# control_v26.net
KiCad netlist of a schematic drawn in EAGLE
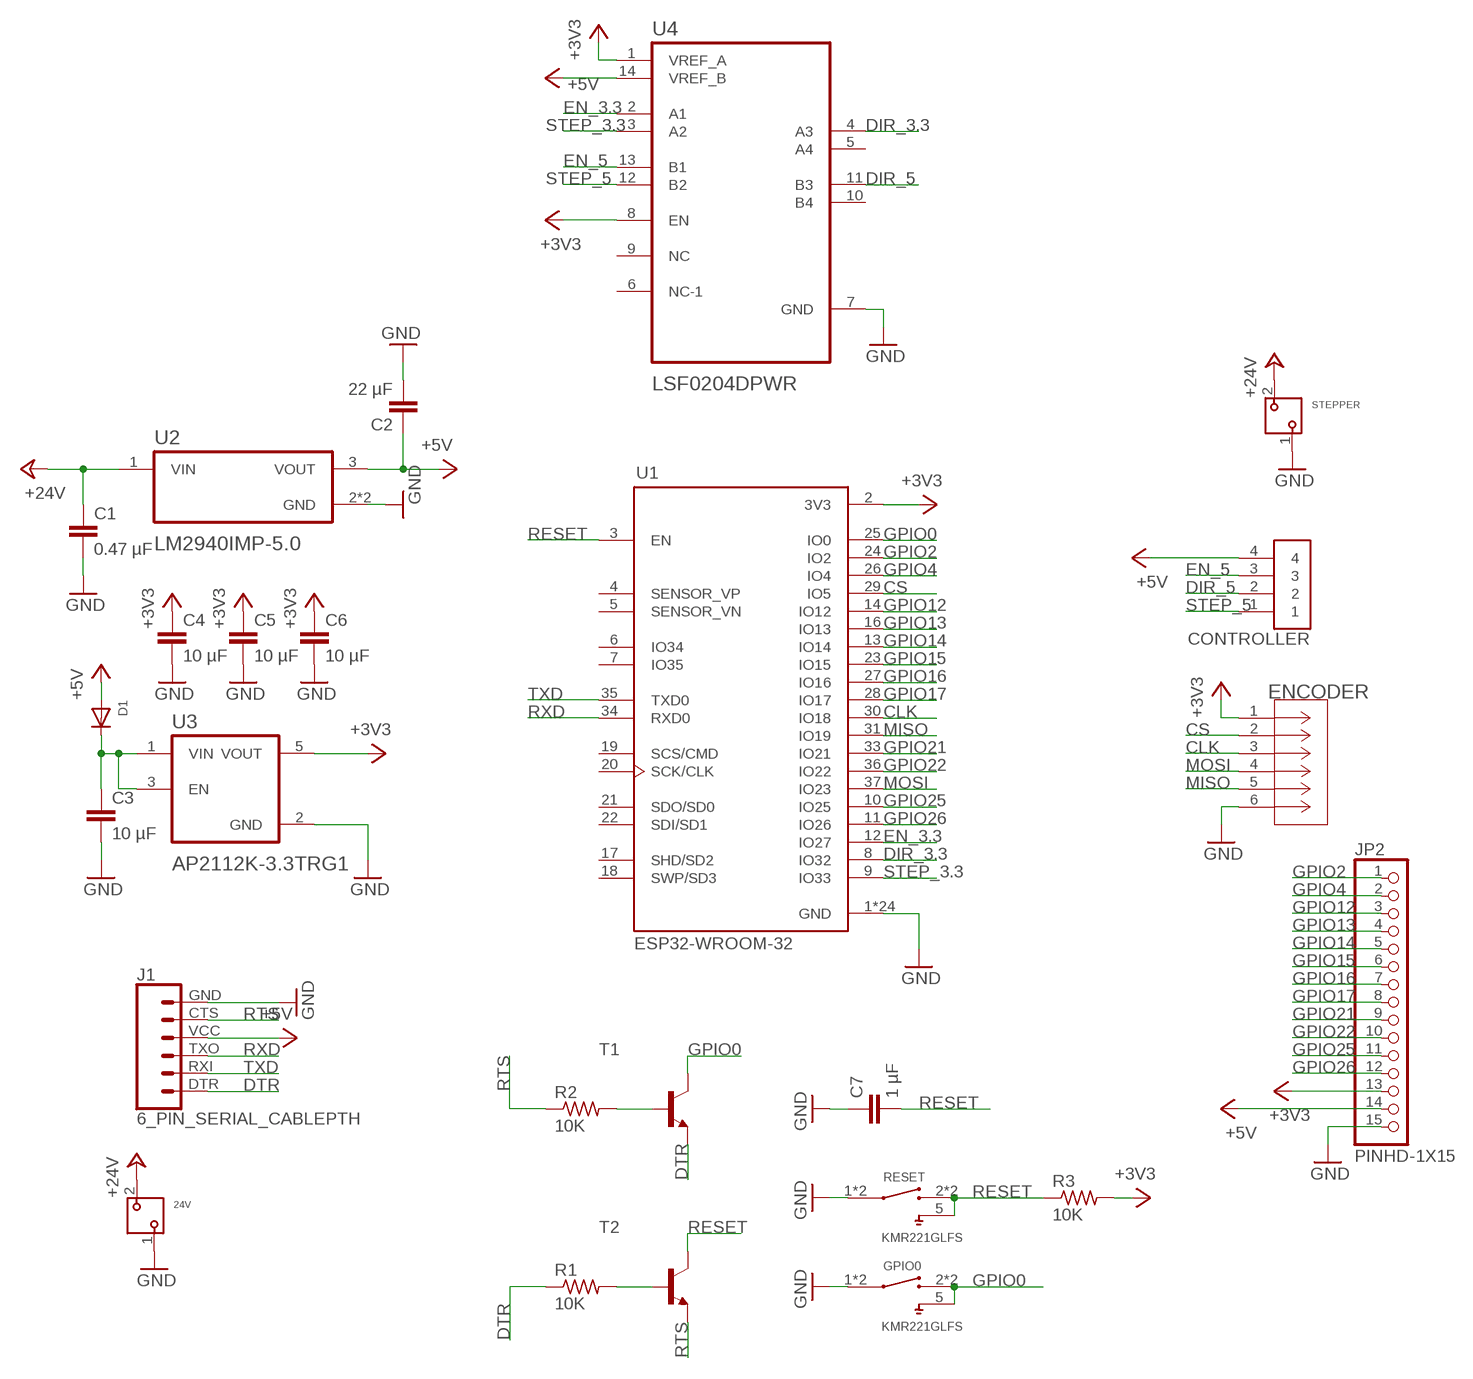
[diagram p0: schematic, sheet 1]

(export (version "E")
  (design (tool "Eeschema 10.0.6"))
  (components
    (comp (ref "24V")
      (value "691412320002")
      (footprint "eagle-import:691412320002")
      (fields (field (name "MF") "Wurth Electronics"))
      (libsource (lib "eagle-import") (part "691412320002"))
    )
    (comp (ref "C1")
      (value "0.47 µF")
      (footprint "eagle-import:C0805")
      (libsource (lib "eagle-import") (part "C-EUC0805"))
    )
    (comp (ref "C2")
      (value "22 µF")
      (footprint "eagle-import:C0805")
      (libsource (lib "eagle-import") (part "C-EUC0805"))
    )
    (comp (ref "C3")
      (value "10 µF")
      (footprint "eagle-import:C0805")
      (libsource (lib "eagle-import") (part "C-EUC0805"))
    )
    (comp (ref "C4")
      (value "10 µF")
      (footprint "eagle-import:C0805")
      (libsource (lib "eagle-import") (part "C-EUC0805"))
    )
    (comp (ref "C5")
      (value "10 µF")
      (footprint "eagle-import:C0805")
      (libsource (lib "eagle-import") (part "C-EUC0805"))
    )
    (comp (ref "C6")
      (value "10 µF")
      (footprint "eagle-import:C0805")
      (libsource (lib "eagle-import") (part "C-EUC0805"))
    )
    (comp (ref "C7")
      (value "1 µF")
      (footprint "eagle-import:C0805")
      (libsource (lib "eagle-import") (part "C-EUC0805"))
    )
    (comp (ref "CONTROLLER")
      (value "B4B-XH-A(LF)(SN)")
      (footprint "eagle-import:JST_B4B-XH-A(LF)(SN)")
      (fields (field (name "DIGI-KEY_PART_NUMBER") "455-2249-ND") (field (name "MF") "JST Sales"))
      (libsource (lib "eagle-import") (part "B4B-XH-A(LF)(SN)"))
    )
    (comp (ref "D1")
      (value "DIODESOD-123")
      (footprint "eagle-import:SOD-123")
      (libsource (lib "eagle-import") (part "DIODESOD-123"))
    )
    (comp (ref "ENCODER")
      (value "B6B-XH-A_(LF)(SN)")
      (footprint "eagle-import:CONN_B6B-XH-A_JST")
      (fields
        (field (name "MANUFACTURER_PART_NUMBER") "B6B-XH-A (LF)(SN)")
        (field (name "COPYRIGHT") "Copyright (C) 2018 Accelerated Designs. All rights reserved")
      )
      (libsource (lib "eagle-import") (part "B6B-XH-A_(LF)(SN)"))
    )
    (comp (ref "GPIO0")
      (value "KMR221GLFS")
      (footprint "eagle-import:SW_KMR221GLFS")
      (fields (field (name "DIGI-KEY_PART_NUMBER") "401-1427-1-ND") (field (name "MF") "C&K"))
      (libsource (lib "eagle-import") (part "KMR221GLFS"))
    )
    (comp (ref "J1")
      (value "6_PIN_SERIAL_CABLEPTH")
      (footprint "eagle-import:FTDI_BASIC")
      (libsource (lib "eagle-import") (part "6_PIN_SERIAL_CABLEPTH"))
    )
    (comp (ref "JP2")
      (value "PINHD-1X15")
      (footprint "eagle-import:1X15")
      (libsource (lib "eagle-import") (part "PINHD-1X15"))
    )
    (comp (ref "R1")
      (value "10K")
      (footprint "eagle-import:R0805")
      (libsource (lib "eagle-import") (part "R-US_R0805"))
    )
    (comp (ref "R2")
      (value "10K")
      (footprint "eagle-import:R0805")
      (libsource (lib "eagle-import") (part "R-US_R0805"))
    )
    (comp (ref "R3")
      (value "10K")
      (footprint "eagle-import:R0805")
      (libsource (lib "eagle-import") (part "R-US_R0805"))
    )
    (comp (ref "RESET")
      (value "KMR221GLFS")
      (footprint "eagle-import:SW_KMR221GLFS")
      (fields (field (name "DIGI-KEY_PART_NUMBER") "401-1427-1-ND") (field (name "MF") "C&K"))
      (libsource (lib "eagle-import") (part "KMR221GLFS"))
    )
    (comp (ref "STEPPER")
      (value "691412320002")
      (footprint "eagle-import:691412320002")
      (fields (field (name "MF") "Wurth Electronics"))
      (libsource (lib "eagle-import") (part "691412320002"))
    )
    (comp (ref "T1")
      (value "MMBT2222ALT1-NPN-SOT23-BEC")
      (footprint "eagle-import:SOT23-BEC")
      (libsource (lib "eagle-import") (part "-NPN-SOT23-BECMMBT2222ALT1"))
    )
    (comp (ref "T2")
      (value "MMBT2222ALT1-NPN-SOT23-BEC")
      (footprint "eagle-import:SOT23-BEC")
      (libsource (lib "eagle-import") (part "-NPN-SOT23-BECMMBT2222ALT1"))
    )
    (comp (ref "U1")
      (value "ESP32-WROOM-32")
      (footprint "eagle-import:MODULE_ESP32-WROOM-32")
      (fields (field (name "DIGI-KEY_PART_NUMBER") "1904-1010-1-ND") (field (name "MF") "Espressif Systems"))
      (libsource (lib "eagle-import") (part "ESP32-WROOM-32"))
    )
    (comp (ref "U2")
      (value "LM2940IMP-5.0")
      (footprint "eagle-import:SOT230P700X180-4N")
      (fields
        (field (name "DIGI-KEY_PART_NUMBER") "LM2940IMP-5.0/NOPBCT-ND")
        (field (name "MF") "Texas Instruments")
        (field (name "MP") "LM2940IMP-5.0/NOPB")
      )
      (libsource (lib "eagle-import") (part "LM2940IMP-5.0"))
    )
    (comp (ref "U3")
      (value "AP2112K-3.3TRG1")
      (footprint "eagle-import:SOT95P285X140-5N")
      (fields
        (field (name "DIGI-KEY_PART_NUMBER") "AP2112K-3.3TRG1DICT-ND")
        (field (name "MF") "Diodes Inc.")
      )
      (libsource (lib "eagle-import") (part "AP2112K-3.3TRG1"))
    )
    (comp (ref "U4")
      (value "LSF0204DPWR")
      (footprint "eagle-import:SOP65P640X120-14N")
      (fields (field (name "DIGI-KEY_PART_NUMBER") "296-40400-1-ND") (field (name "MF") "Texas Instruments"))
      (libsource (lib "eagle-import") (part "LSF0204DPWR"))
    )
  )
  (nets
    (net (code "1") (name "+3V3") (class "Default")
      (node (ref "C4") (pin "1") (pinfunction "1_1") (pintype "passive"))
      (node (ref "C5") (pin "1") (pinfunction "1_1") (pintype "passive"))
      (node (ref "C6") (pin "1") (pinfunction "1_1") (pintype "passive"))
      (node (ref "ENCODER") (pin "1") (pinfunction "1_1") (pintype "passive"))
      (node (ref "JP2") (pin "13") (pinfunction "13_13") (pintype "passive"))
      (node (ref "R3") (pin "2") (pinfunction "2_2") (pintype "passive"))
      (node (ref "U1") (pin "2") (pinfunction "3V3_2") (pintype "power_in"))
      (node (ref "U3") (pin "5") (pinfunction "VOUT_5") (pintype "power_in"))
      (node (ref "U4") (pin "1") (pinfunction "VREF_A_1") (pintype "input"))
      (node (ref "U4") (pin "8") (pinfunction "EN_8") (pintype "bidirectional"))
    )
    (net (code "2") (name "+5V") (class "Default")
      (node (ref "C2") (pin "1") (pinfunction "1_1") (pintype "passive"))
      (node (ref "CONTROLLER") (pin "4") (pinfunction "4_4") (pintype "passive"))
      (node (ref "D1") (pin "A") (pinfunction "A_A") (pintype "passive"))
      (node (ref "J1") (pin "VCC") (pinfunction "4_VCC") (pintype "passive"))
      (node (ref "JP2") (pin "14") (pinfunction "14_14") (pintype "passive"))
      (node (ref "U2") (pin "3") (pinfunction "VOUT_3") (pintype "output"))
      (node (ref "U4") (pin "14") (pinfunction "VREF_B_14") (pintype "input"))
    )
    (net (code "3") (name "+24V") (class "Default")
      (node (ref "24V") (pin "2") (pinfunction "2_2") (pintype "passive"))
      (node (ref "C1") (pin "1") (pinfunction "1_1") (pintype "passive"))
      (node (ref "STEPPER") (pin "2") (pinfunction "2_2") (pintype "passive"))
      (node (ref "U2") (pin "1") (pinfunction "VIN_1") (pintype "input"))
    )
    (net (code "4") (name "/CLK") (class "Default")
      (node (ref "ENCODER") (pin "3") (pinfunction "3_3") (pintype "passive"))
      (node (ref "U1") (pin "30") (pinfunction "IO18_30") (pintype "bidirectional"))
    )
    (net (code "5") (name "/CS") (class "Default")
      (node (ref "ENCODER") (pin "2") (pinfunction "2_2") (pintype "passive"))
      (node (ref "U1") (pin "29") (pinfunction "IO5_29") (pintype "bidirectional"))
    )
    (net (code "6") (name "/DIR_3.3") (class "Default")
      (node (ref "U1") (pin "8") (pinfunction "IO32_8") (pintype "bidirectional"))
      (node (ref "U4") (pin "4") (pinfunction "A3_4") (pintype "bidirectional"))
    )
    (net (code "7") (name "/DIR_5") (class "Default")
      (node (ref "CONTROLLER") (pin "2") (pinfunction "2_2") (pintype "passive"))
      (node (ref "U4") (pin "11") (pinfunction "B3_11") (pintype "bidirectional"))
    )
    (net (code "8") (name "/DTR") (class "Default")
      (node (ref "J1") (pin "DTR") (pinfunction "1_DTR") (pintype "passive"))
      (node (ref "R1") (pin "1") (pinfunction "1_1") (pintype "passive"))
      (node (ref "T1") (pin "E") (pinfunction "E_E") (pintype "passive"))
    )
    (net (code "9") (name "/EN_3.3") (class "Default")
      (node (ref "U1") (pin "12") (pinfunction "IO27_12") (pintype "bidirectional"))
      (node (ref "U4") (pin "2") (pinfunction "A1_2") (pintype "bidirectional"))
    )
    (net (code "10") (name "/EN_5") (class "Default")
      (node (ref "CONTROLLER") (pin "3") (pinfunction "3_3") (pintype "passive"))
      (node (ref "U4") (pin "13") (pinfunction "B1_13") (pintype "bidirectional"))
    )
    (net (code "11") (name "/GPIO0") (class "Default")
      (node (ref "GPIO0") (pin "2") (pinfunction "3_2") (pintype "passive"))
      (node (ref "GPIO0") (pin "3") (pinfunction "3_3") (pintype "passive"))
      (node (ref "GPIO0") (pin "5") (pinfunction "5_5") (pintype "passive"))
      (node (ref "T1") (pin "C") (pinfunction "C_C") (pintype "passive"))
      (node (ref "U1") (pin "25") (pinfunction "IO0_25") (pintype "bidirectional"))
    )
    (net (code "12") (name "/GPIO2") (class "Default")
      (node (ref "JP2") (pin "1") (pinfunction "1_1") (pintype "passive"))
      (node (ref "U1") (pin "24") (pinfunction "IO2_24") (pintype "bidirectional"))
    )
    (net (code "13") (name "/GPIO4") (class "Default")
      (node (ref "JP2") (pin "2") (pinfunction "2_2") (pintype "passive"))
      (node (ref "U1") (pin "26") (pinfunction "IO4_26") (pintype "bidirectional"))
    )
    (net (code "14") (name "/GPIO12") (class "Default")
      (node (ref "JP2") (pin "3") (pinfunction "3_3") (pintype "passive"))
      (node (ref "U1") (pin "14") (pinfunction "IO12_14") (pintype "bidirectional"))
    )
    (net (code "15") (name "/GPIO13") (class "Default")
      (node (ref "JP2") (pin "4") (pinfunction "4_4") (pintype "passive"))
      (node (ref "U1") (pin "16") (pinfunction "IO13_16") (pintype "bidirectional"))
    )
    (net (code "16") (name "/GPIO14") (class "Default")
      (node (ref "JP2") (pin "5") (pinfunction "5_5") (pintype "passive"))
      (node (ref "U1") (pin "13") (pinfunction "IO14_13") (pintype "bidirectional"))
    )
    (net (code "17") (name "/GPIO15") (class "Default")
      (node (ref "JP2") (pin "6") (pinfunction "6_6") (pintype "passive"))
      (node (ref "U1") (pin "23") (pinfunction "IO15_23") (pintype "bidirectional"))
    )
    (net (code "18") (name "/GPIO16") (class "Default")
      (node (ref "JP2") (pin "7") (pinfunction "7_7") (pintype "passive"))
      (node (ref "U1") (pin "27") (pinfunction "IO16_27") (pintype "bidirectional"))
    )
    (net (code "19") (name "/GPIO17") (class "Default")
      (node (ref "JP2") (pin "8") (pinfunction "8_8") (pintype "passive"))
      (node (ref "U1") (pin "28") (pinfunction "IO17_28") (pintype "bidirectional"))
    )
    (net (code "20") (name "/GPIO21") (class "Default")
      (node (ref "JP2") (pin "9") (pinfunction "9_9") (pintype "passive"))
      (node (ref "U1") (pin "33") (pinfunction "IO21_33") (pintype "bidirectional"))
    )
    (net (code "21") (name "/GPIO22") (class "Default")
      (node (ref "JP2") (pin "10") (pinfunction "10_10") (pintype "passive"))
      (node (ref "U1") (pin "36") (pinfunction "IO22_36") (pintype "bidirectional"))
    )
    (net (code "22") (name "/GPIO25") (class "Default")
      (node (ref "JP2") (pin "11") (pinfunction "11_11") (pintype "passive"))
      (node (ref "U1") (pin "10") (pinfunction "IO25_10") (pintype "bidirectional"))
    )
    (net (code "23") (name "/GPIO26") (class "Default")
      (node (ref "JP2") (pin "12") (pinfunction "12_12") (pintype "passive"))
      (node (ref "U1") (pin "11") (pinfunction "IO26_11") (pintype "bidirectional"))
    )
    (net (code "24") (name "/MISO") (class "Default")
      (node (ref "ENCODER") (pin "5") (pinfunction "5_5") (pintype "passive"))
      (node (ref "U1") (pin "31") (pinfunction "IO19_31") (pintype "bidirectional"))
    )
    (net (code "25") (name "/MOSI") (class "Default")
      (node (ref "ENCODER") (pin "4") (pinfunction "4_4") (pintype "passive"))
      (node (ref "U1") (pin "37") (pinfunction "IO23_37") (pintype "bidirectional"))
    )
    (net (code "26") (name "/RESET") (class "Default")
      (node (ref "C7") (pin "2") (pinfunction "2_2") (pintype "passive"))
      (node (ref "R3") (pin "1") (pinfunction "1_1") (pintype "passive"))
      (node (ref "RESET") (pin "2") (pinfunction "3_2") (pintype "passive"))
      (node (ref "RESET") (pin "3") (pinfunction "3_3") (pintype "passive"))
      (node (ref "RESET") (pin "5") (pinfunction "5_5") (pintype "passive"))
      (node (ref "T2") (pin "C") (pinfunction "C_C") (pintype "passive"))
      (node (ref "U1") (pin "3") (pinfunction "EN_3") (pintype "input"))
    )
    (net (code "27") (name "/RTS") (class "Default")
      (node (ref "J1") (pin "CTS") (pinfunction "5_CTS") (pintype "passive"))
      (node (ref "R2") (pin "1") (pinfunction "1_1") (pintype "passive"))
      (node (ref "T2") (pin "E") (pinfunction "E_E") (pintype "passive"))
    )
    (net (code "28") (name "/RXD") (class "Default")
      (node (ref "J1") (pin "TXO") (pinfunction "3_TXO") (pintype "passive"))
      (node (ref "U1") (pin "34") (pinfunction "RXD0_34") (pintype "bidirectional"))
    )
    (net (code "29") (name "/STEP_3.3") (class "Default")
      (node (ref "U1") (pin "9") (pinfunction "IO33_9") (pintype "bidirectional"))
      (node (ref "U4") (pin "3") (pinfunction "A2_3") (pintype "bidirectional"))
    )
    (net (code "30") (name "/STEP_5") (class "Default")
      (node (ref "CONTROLLER") (pin "1") (pinfunction "1_1") (pintype "passive"))
      (node (ref "U4") (pin "12") (pinfunction "B2_12") (pintype "bidirectional"))
    )
    (net (code "31") (name "/TXD") (class "Default")
      (node (ref "J1") (pin "RXI") (pinfunction "2_RXI") (pintype "passive"))
      (node (ref "U1") (pin "35") (pinfunction "TXD0_35") (pintype "bidirectional"))
    )
    (net (code "32") (name "GND") (class "Default")
      (node (ref "24V") (pin "1") (pinfunction "1_1") (pintype "passive"))
      (node (ref "C1") (pin "2") (pinfunction "2_2") (pintype "passive"))
      (node (ref "C2") (pin "2") (pinfunction "2_2") (pintype "passive"))
      (node (ref "C3") (pin "2") (pinfunction "2_2") (pintype "passive"))
      (node (ref "C4") (pin "2") (pinfunction "2_2") (pintype "passive"))
      (node (ref "C5") (pin "2") (pinfunction "2_2") (pintype "passive"))
      (node (ref "C6") (pin "2") (pinfunction "2_2") (pintype "passive"))
      (node (ref "C7") (pin "1") (pinfunction "1_1") (pintype "passive"))
      (node (ref "ENCODER") (pin "6") (pinfunction "6_6") (pintype "passive"))
      (node (ref "GPIO0") (pin "1") (pinfunction "1_1") (pintype "passive"))
      (node (ref "GPIO0") (pin "4") (pinfunction "1_4") (pintype "passive"))
      (node (ref "J1") (pin "GND") (pinfunction "6_GND") (pintype "passive"))
      (node (ref "JP2") (pin "15") (pinfunction "15_15") (pintype "passive"))
      (node (ref "RESET") (pin "1") (pinfunction "1_1") (pintype "passive"))
      (node (ref "RESET") (pin "4") (pinfunction "1_4") (pintype "passive"))
      (node (ref "STEPPER") (pin "1") (pinfunction "1_1") (pintype "passive"))
      (node (ref "U1") (pin "1") (pinfunction "GND_1") (pintype "power_in"))
      (node (ref "U1") (pin "15") (pinfunction "GND_15") (pintype "power_in"))
      (node (ref "U1") (pin "38") (pinfunction "GND_38") (pintype "power_in"))
      (node (ref "U1") (pin "39_1") (pinfunction "GND_39_1") (pintype "power_in"))
      (node (ref "U1") (pin "39_10") (pinfunction "GND_39_10") (pintype "power_in"))
      (node (ref "U1") (pin "39_11") (pinfunction "GND_39_11") (pintype "power_in"))
      (node (ref "U1") (pin "39_12") (pinfunction "GND_39_12") (pintype "power_in"))
      (node (ref "U1") (pin "39_13") (pinfunction "GND_39_13") (pintype "power_in"))
      (node (ref "U1") (pin "39_14") (pinfunction "GND_39_14") (pintype "power_in"))
      (node (ref "U1") (pin "39_15") (pinfunction "GND_39_15") (pintype "power_in"))
      (node (ref "U1") (pin "39_16") (pinfunction "GND_39_16") (pintype "power_in"))
      (node (ref "U1") (pin "39_17") (pinfunction "GND_39_17") (pintype "power_in"))
      (node (ref "U1") (pin "39_18") (pinfunction "GND_39_18") (pintype "power_in"))
      (node (ref "U1") (pin "39_19") (pinfunction "GND_39_19") (pintype "power_in"))
      (node (ref "U1") (pin "39_2") (pinfunction "GND_39_2") (pintype "power_in"))
      (node (ref "U1") (pin "39_20") (pinfunction "GND_39_20") (pintype "power_in"))
      (node (ref "U1") (pin "39_21") (pinfunction "GND_39_21") (pintype "power_in"))
      (node (ref "U1") (pin "39_3") (pinfunction "GND_39_3") (pintype "power_in"))
      (node (ref "U1") (pin "39_4") (pinfunction "GND_39_4") (pintype "power_in"))
      (node (ref "U1") (pin "39_5") (pinfunction "GND_39_5") (pintype "power_in"))
      (node (ref "U1") (pin "39_6") (pinfunction "GND_39_6") (pintype "power_in"))
      (node (ref "U1") (pin "39_7") (pinfunction "GND_39_7") (pintype "power_in"))
      (node (ref "U1") (pin "39_8") (pinfunction "GND_39_8") (pintype "power_in"))
      (node (ref "U1") (pin "39_9") (pinfunction "GND_39_9") (pintype "power_in"))
      (node (ref "U2") (pin "2") (pinfunction "GND_2") (pintype "power_in"))
      (node (ref "U2") (pin "4") (pinfunction "GND_4") (pintype "power_in"))
      (node (ref "U3") (pin "2") (pinfunction "GND_2") (pintype "power_in"))
      (node (ref "U4") (pin "7") (pinfunction "GND_7") (pintype "power_in"))
    )
    (net (code "33") (name "Net-(R1-Pad2)") (class "Default")
      (node (ref "R1") (pin "2") (pinfunction "2_2") (pintype "passive"))
      (node (ref "T2") (pin "B") (pinfunction "B_B") (pintype "passive"))
    )
    (net (code "34") (name "Net-(R2-Pad2)") (class "Default")
      (node (ref "R2") (pin "2") (pinfunction "2_2") (pintype "passive"))
      (node (ref "T1") (pin "B") (pinfunction "B_B") (pintype "passive"))
    )
    (net (code "35") (name "Net-(U3-EN)") (class "Default")
      (node (ref "C3") (pin "1") (pinfunction "1_1") (pintype "passive"))
      (node (ref "D1") (pin "C") (pinfunction "C_C") (pintype "passive"))
      (node (ref "U3") (pin "1") (pinfunction "VIN_1") (pintype "power_in"))
      (node (ref "U3") (pin "3") (pinfunction "EN_3") (pintype "input"))
    )
    (net (code "36") (name "unconnected-(U1-IO34-Pad6)") (class "Default")
      (node (ref "U1") (pin "6") (pinfunction "IO34_6") (pintype "input"))
    )
    (net (code "37") (name "unconnected-(U1-IO35-Pad7)") (class "Default")
      (node (ref "U1") (pin "7") (pinfunction "IO35_7") (pintype "input"))
    )
    (net (code "38") (name "unconnected-(U1-SCK{slash}CLK-Pad20)") (class "Default")
      (node (ref "U1") (pin "20") (pinfunction "SCK/CLK_20") (pintype "bidirectional"))
    )
    (net (code "39") (name "unconnected-(U1-SCS{slash}CMD-Pad19)") (class "Default")
      (node (ref "U1") (pin "19") (pinfunction "SCS/CMD_19") (pintype "bidirectional"))
    )
    (net (code "40") (name "unconnected-(U1-SDI{slash}SD1-Pad22)") (class "Default")
      (node (ref "U1") (pin "22") (pinfunction "SDI/SD1_22") (pintype "bidirectional"))
    )
    (net (code "41") (name "unconnected-(U1-SDO{slash}SD0-Pad21)") (class "Default")
      (node (ref "U1") (pin "21") (pinfunction "SDO/SD0_21") (pintype "bidirectional"))
    )
    (net (code "42") (name "unconnected-(U1-SENSOR_VN-Pad5)") (class "Default")
      (node (ref "U1") (pin "5") (pinfunction "SENSOR_VN_5") (pintype "input"))
    )
    (net (code "43") (name "unconnected-(U1-SENSOR_VP-Pad4)") (class "Default")
      (node (ref "U1") (pin "4") (pinfunction "SENSOR_VP_4") (pintype "input"))
    )
    (net (code "44") (name "unconnected-(U1-SHD{slash}SD2-Pad17)") (class "Default")
      (node (ref "U1") (pin "17") (pinfunction "SHD/SD2_17") (pintype "bidirectional"))
    )
    (net (code "45") (name "unconnected-(U1-SWP{slash}SD3-Pad18)") (class "Default")
      (node (ref "U1") (pin "18") (pinfunction "SWP/SD3_18") (pintype "bidirectional"))
    )
    (net (code "46") (name "unconnected-(U4-A4-Pad5)") (class "Default")
      (node (ref "U4") (pin "5") (pinfunction "A4_5") (pintype "bidirectional"))
    )
    (net (code "47") (name "unconnected-(U4-B4-Pad10)") (class "Default")
      (node (ref "U4") (pin "10") (pinfunction "B4_10") (pintype "bidirectional"))
    )
    (net (code "48") (name "unconnected-(U4-NC-1-Pad6)") (class "Default")
      (node (ref "U4") (pin "6") (pinfunction "NC-1_6") (pintype "bidirectional"))
    )
    (net (code "49") (name "unconnected-(U4-NC-Pad9)") (class "Default")
      (node (ref "U4") (pin "9") (pinfunction "NC_9") (pintype "bidirectional"))
    )
  )
)
